# PSU.net
KiCad netlist of a schematic drawn in Altium Designer
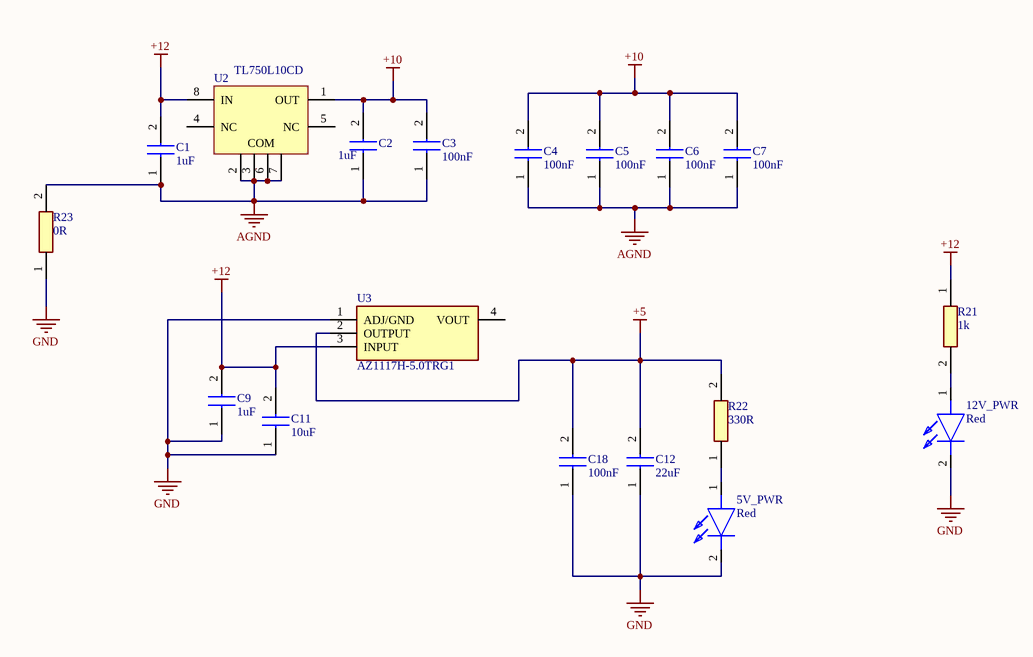
[diagram p0: PSU.SchDoc]

(export (version "E")
  (design (tool "Eeschema 10.0.6"))
  (components
    (comp (ref "5V_PWR")
      (value "Red")
      (footprint "SamacSys:APT2012SECKJ3PRV")
      (description "LED")
      (fields (field (name "MANUFACTURER_PART_NUMBER") "APT2012SECK/J3-PRV"))
      (libsource (lib "*") (part "APT2012SECK_J3-PRV"))
    )
    (comp (ref "12V_PWR")
      (value "Red")
      (footprint "SamacSys:APT2012SECKJ3PRV")
      (description "LED")
      (fields (field (name "MANUFACTURER_PART_NUMBER") "APT2012SECK/J3-PRV"))
      (libsource (lib "*") (part "APT2012SECK_J3-PRV"))
    )
    (comp (ref "C1")
      (value "1uF")
      (footprint "SamacSys:CAPC1005X55N")
      (description "Capacitor")
      (fields (field (name "MANUFACTURER_PART_NUMBER") "GRT155C81E105KE13D"))
      (libsource (lib "*") (part "GRT155C81E105KE13D"))
    )
    (comp (ref "C2")
      (value "1uF")
      (footprint "SamacSys:CAPC1005X55N")
      (description "Capacitor")
      (fields (field (name "MANUFACTURER_PART_NUMBER") "GRT155C81E105KE13D"))
      (libsource (lib "*") (part "GRT155C81E105KE13D"))
    )
    (comp (ref "C3")
      (value "100nF")
      (footprint "SamacSys:CAPC1005X55N")
      (description "Capacitor")
      (fields (field (name "MANUFACTURER_PART_NUMBER") "GCM155L81E104KE02D"))
      (libsource (lib "*") (part "GCM155L81E104KE02D"))
    )
    (comp (ref "C4")
      (value "100nF")
      (footprint "SamacSys:CAPC1005X55N")
      (description "Capacitor")
      (fields (field (name "MANUFACTURER_PART_NUMBER") "GCM155L81E104KE02D"))
      (libsource (lib "*") (part "GCM155L81E104KE02D"))
    )
    (comp (ref "C5")
      (value "100nF")
      (footprint "SamacSys:CAPC1005X55N")
      (description "Capacitor")
      (fields (field (name "MANUFACTURER_PART_NUMBER") "GCM155L81E104KE02D"))
      (libsource (lib "*") (part "GCM155L81E104KE02D"))
    )
    (comp (ref "C6")
      (value "100nF")
      (footprint "SamacSys:CAPC1005X55N")
      (description "Capacitor")
      (fields (field (name "MANUFACTURER_PART_NUMBER") "GCM155L81E104KE02D"))
      (libsource (lib "*") (part "GCM155L81E104KE02D"))
    )
    (comp (ref "C7")
      (value "100nF")
      (footprint "SamacSys:CAPC1005X55N")
      (description "Capacitor")
      (fields (field (name "MANUFACTURER_PART_NUMBER") "GCM155L81E104KE02D"))
      (libsource (lib "*") (part "GCM155L81E104KE02D"))
    )
    (comp (ref "C9")
      (value "1uF")
      (footprint "SamacSys:CAPC1005X55N")
      (description "Capacitor")
      (fields (field (name "MANUFACTURER_PART_NUMBER") "GRT155C81E105KE13D"))
      (libsource (lib "*") (part "GRT155C81E105KE13D"))
    )
    (comp (ref "C11")
      (value "10uF")
      (footprint "SamacSys:C1608_Commercial")
      (description "Capacitor")
      (fields (field (name "MANUFACTURER_PART_NUMBER") "C1608JB1E106M080AC"))
      (libsource (lib "*") (part "C1608JB1E106M080AC"))
    )
    (comp (ref "C12")
      (value "22uF")
      (footprint "SamacSys:C3216_Commercial")
      (description "Capacitor")
      (fields (field (name "MANUFACTURER_PART_NUMBER") "C3216X6S1E226M160AC"))
      (libsource (lib "*") (part "C3216X6S1E226M160AC"))
    )
    (comp (ref "C18")
      (value "100nF")
      (footprint "SamacSys:CAPC1005X55N")
      (description "Capacitor")
      (fields (field (name "MANUFACTURER_PART_NUMBER") "GCM155L81E104KE02D"))
      (libsource (lib "*") (part "GCM155L81E104KE02D"))
    )
    (comp (ref "R21")
      (value "1k")
      (footprint "SamacSys:ERA2V_(0402)")
      (description "Resistor")
      (fields (field (name "MANUFACTURER_PART_NUMBER") "ERA-2VEB1001X"))
      (libsource (lib "*") (part "ERA-2VEB1001X"))
    )
    (comp (ref "R22")
      (value "330R")
      (footprint "SamacSys:ERJ2RKD1004X")
      (description "Resistor")
      (fields (field (name "MANUFACTURER_PART_NUMBER") "ERJ-2RHD3300X"))
      (libsource (lib "*") (part "ERJ-2RHD3300X"))
    )
    (comp (ref "R23")
      (value "0R")
      (footprint "SamacSys:RESC1005X40N")
      (description "Resistor")
      (fields (field (name "MANUFACTURER_PART_NUMBER") "RC0402JR-130RL"))
      (libsource (lib "*") (part "RC0402JR-130RL"))
    )
    (comp (ref "U2")
      (value "TL750L10CD")
      (footprint "D0008A_M")
      (fields (field (name "MANUFACTURER") "Texas Instruments"))
      (libsource (lib "Altium Content Vault") (part "TI-TL750L10D8"))
    )
    (comp (ref "U3")
      (value "AZ1117H-5.0TRG1")
      (footprint "SamacSys:SOT230P700X180-4N")
      (description "Integrated Circuit")
      (libsource (lib "*") (part "AZ1117H-5.0TRG1"))
    )
  )
  (nets
    (net (code "1") (name "+5") (class "Default")
      (node (ref "C12") (pin "2") (pinfunction "2_2") (pintype "passive"))
      (node (ref "C18") (pin "2") (pinfunction "2_2") (pintype "passive"))
      (node (ref "R22") (pin "2") (pinfunction "2_2") (pintype "passive"))
      (node (ref "U3") (pin "2") (pinfunction "OUTPUT_2") (pintype "passive"))
    )
    (net (code "2") (name "+10") (class "Default")
      (node (ref "C2") (pin "2") (pinfunction "2_2") (pintype "passive"))
      (node (ref "C3") (pin "2") (pinfunction "2_2") (pintype "passive"))
      (node (ref "C4") (pin "2") (pinfunction "2_2") (pintype "passive"))
      (node (ref "C5") (pin "2") (pinfunction "2_2") (pintype "passive"))
      (node (ref "C6") (pin "2") (pinfunction "2_2") (pintype "passive"))
      (node (ref "C7") (pin "2") (pinfunction "2_2") (pintype "passive"))
      (node (ref "U2") (pin "1") (pinfunction "OUT_1") (pintype "power_in"))
    )
    (net (code "3") (name "+12") (class "Default")
      (node (ref "C1") (pin "2") (pinfunction "2_2") (pintype "passive"))
      (node (ref "C11") (pin "2") (pinfunction "2_2") (pintype "passive"))
      (node (ref "C9") (pin "2") (pinfunction "2_2") (pintype "passive"))
      (node (ref "R21") (pin "1") (pinfunction "1_1") (pintype "passive"))
      (node (ref "U2") (pin "8") (pinfunction "IN_8") (pintype "power_in"))
      (node (ref "U3") (pin "3") (pinfunction "INPUT_3") (pintype "passive"))
    )
    (net (code "4") (name "AGND") (class "Default")
      (node (ref "C1") (pin "1") (pinfunction "1_1") (pintype "passive"))
      (node (ref "C2") (pin "1") (pinfunction "1_1") (pintype "passive"))
      (node (ref "C3") (pin "1") (pinfunction "1_1") (pintype "passive"))
      (node (ref "C4") (pin "1") (pinfunction "1_1") (pintype "passive"))
      (node (ref "C5") (pin "1") (pinfunction "1_1") (pintype "passive"))
      (node (ref "C6") (pin "1") (pinfunction "1_1") (pintype "passive"))
      (node (ref "C7") (pin "1") (pinfunction "1_1") (pintype "passive"))
      (node (ref "R23") (pin "2") (pinfunction "2_2") (pintype "passive"))
      (node (ref "U2") (pin "2") (pinfunction "COM_2") (pintype "power_in"))
      (node (ref "U2") (pin "3") (pinfunction "COM_3") (pintype "power_in"))
      (node (ref "U2") (pin "6") (pinfunction "COM_6") (pintype "power_in"))
      (node (ref "U2") (pin "7") (pinfunction "COM_7") (pintype "power_in"))
    )
    (net (code "5") (name "GND") (class "Default")
      (node (ref "12V_PWR") (pin "2") (pinfunction "K_2") (pintype "passive"))
      (node (ref "5V_PWR") (pin "2") (pinfunction "K_2") (pintype "passive"))
      (node (ref "C11") (pin "1") (pinfunction "1_1") (pintype "passive"))
      (node (ref "C12") (pin "1") (pinfunction "1_1") (pintype "passive"))
      (node (ref "C18") (pin "1") (pinfunction "1_1") (pintype "passive"))
      (node (ref "C9") (pin "1") (pinfunction "1_1") (pintype "passive"))
      (node (ref "R23") (pin "1") (pinfunction "1_1") (pintype "passive"))
      (node (ref "U3") (pin "1") (pinfunction "ADJ/GND_1") (pintype "passive"))
    )
    (net (code "6") (name "Net-(5V_PWR-A)") (class "Default")
      (node (ref "5V_PWR") (pin "1") (pinfunction "A_1") (pintype "passive"))
      (node (ref "R22") (pin "1") (pinfunction "1_1") (pintype "passive"))
    )
    (net (code "7") (name "Net-(12V_PWR-A)") (class "Default")
      (node (ref "12V_PWR") (pin "1") (pinfunction "A_1") (pintype "passive"))
      (node (ref "R21") (pin "2") (pinfunction "2_2") (pintype "passive"))
    )
    (net (code "8") (name "unconnected-(U2-NC-Pad4)") (class "Default")
      (node (ref "U2") (pin "4") (pinfunction "NC_4") (pintype "passive"))
    )
    (net (code "9") (name "unconnected-(U2-NC-Pad5)") (class "Default")
      (node (ref "U2") (pin "5") (pinfunction "NC_5") (pintype "passive"))
    )
    (net (code "10") (name "unconnected-(U3-VOUT-Pad4)") (class "Default")
      (node (ref "U3") (pin "4") (pinfunction "VOUT_4") (pintype "passive"))
    )
  )
)
